# Circuit.net
KiCad netlist of a schematic drawn in EAGLE
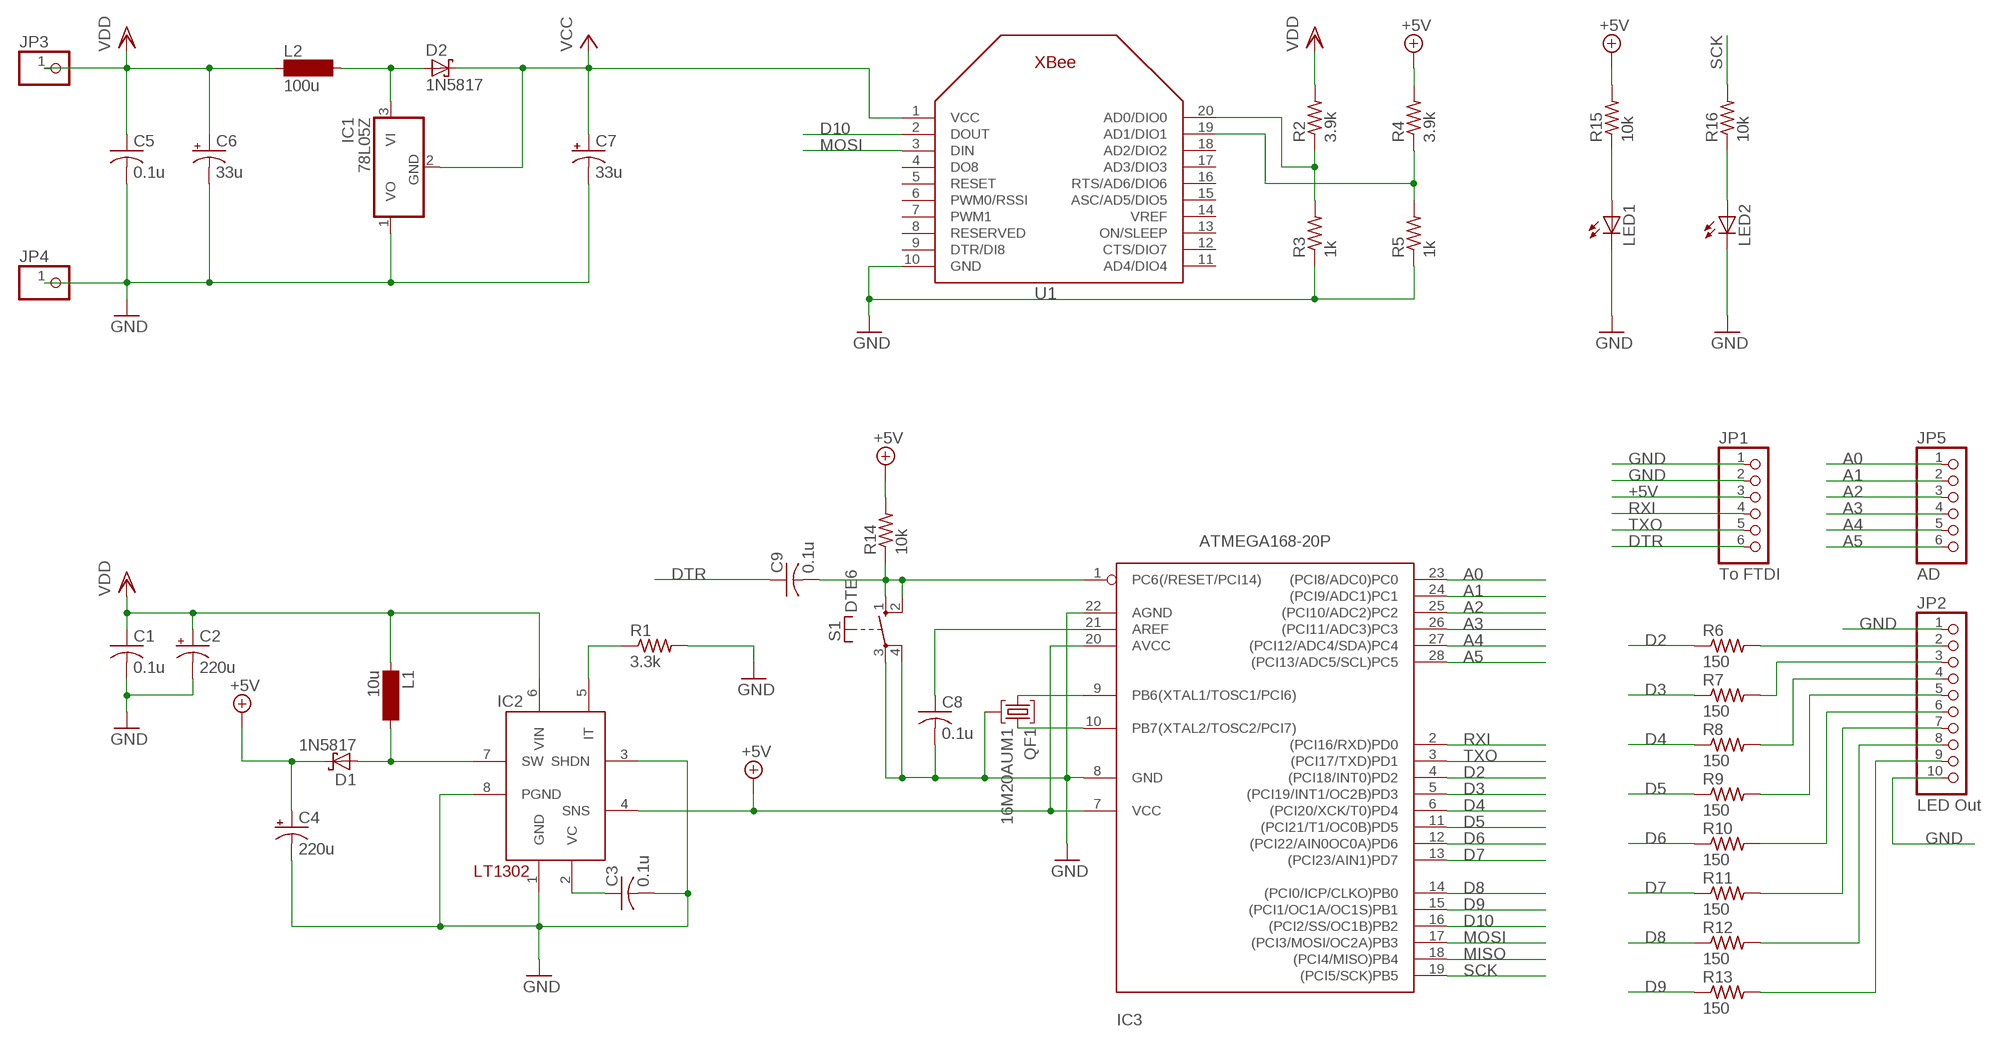
[diagram p0: schematic, sheet 1]

(export (version "E")
  (design (tool "Eeschema 10.0.6"))
  (components
    (comp (ref "C1")
      (value "0.1u")
      (footprint "eagle-import:C050-025X075")
      (libsource (lib "eagle-import") (part "C-US050-025X075"))
    )
    (comp (ref "C2")
      (value "220u")
      (footprint "eagle-import:E2,5-6")
      (libsource (lib "eagle-import") (part "CPOL-USE2.5-6"))
    )
    (comp (ref "C3")
      (value "0.1u")
      (footprint "eagle-import:C050-025X075")
      (libsource (lib "eagle-import") (part "C-US050-025X075"))
    )
    (comp (ref "C4")
      (value "220u")
      (footprint "eagle-import:E2,5-6")
      (libsource (lib "eagle-import") (part "CPOL-USE2.5-6"))
    )
    (comp (ref "C5")
      (value "0.1u")
      (footprint "eagle-import:C050-025X075")
      (libsource (lib "eagle-import") (part "C-US050-025X075"))
    )
    (comp (ref "C6")
      (value "33u")
      (footprint "eagle-import:E2,5-5")
      (libsource (lib "eagle-import") (part "CPOL-USE2.5-5"))
    )
    (comp (ref "C7")
      (value "33u")
      (footprint "eagle-import:E2,5-5")
      (libsource (lib "eagle-import") (part "CPOL-USE2.5-5"))
    )
    (comp (ref "C8")
      (value "0.1u")
      (footprint "eagle-import:C050-025X075")
      (libsource (lib "eagle-import") (part "C-US050-025X075"))
    )
    (comp (ref "C9")
      (value "0.1u")
      (footprint "eagle-import:C050-025X075")
      (libsource (lib "eagle-import") (part "C-US050-025X075"))
    )
    (comp (ref "D1")
      (value "1N5817")
      (footprint "eagle-import:DO35-7")
      (libsource (lib "eagle-import") (part "SCHOTTKY-DIODEDO35-7"))
    )
    (comp (ref "D2")
      (value "1N5817")
      (footprint "eagle-import:DO41-10")
      (libsource (lib "eagle-import") (part "BAT49"))
    )
    (comp (ref "IC1")
      (value "78L05Z")
      (footprint "eagle-import:TO92")
      (libsource (lib "eagle-import") (part "78ZL05"))
    )
    (comp (ref "IC2")
      (value "LT1302")
      (footprint "eagle-import:DIL08")
      (libsource (lib "eagle-import") (part "LT1302"))
    )
    (comp (ref "IC3")
      (value "ATMEGA168-20P")
      (footprint "eagle-import:DIL28-3")
      (libsource (lib "eagle-import") (part "ATMEGA168P-20"))
    )
    (comp (ref "JP1")
      (value "To FTDI")
      (footprint "eagle-import:1X06")
      (libsource (lib "eagle-import") (part "PINHD-1X6"))
    )
    (comp (ref "JP2")
      (value "LED Out")
      (footprint "eagle-import:1X10-BIG")
      (libsource (lib "eagle-import") (part "PINHD-1X10"))
    )
    (comp (ref "JP3")
      (value "PINHD-1X1")
      (footprint "eagle-import:1X01")
      (libsource (lib "eagle-import") (part "PINHD-1X1"))
    )
    (comp (ref "JP4")
      (value "PINHD-1X1")
      (footprint "eagle-import:1X01")
      (libsource (lib "eagle-import") (part "PINHD-1X1"))
    )
    (comp (ref "JP5")
      (value "AD")
      (footprint "eagle-import:1X06")
      (libsource (lib "eagle-import") (part "PINHD-1X6"))
    )
    (comp (ref "L1")
      (value "10u")
      (footprint "eagle-import:BS11")
      (libsource (lib "eagle-import") (part "BS11"))
    )
    (comp (ref "L2")
      (value "100u")
      (footprint "eagle-import:BS11")
      (fields (field (name "OC_FARNELL") "unknown") (field (name "OC_NEWARK") "unknown"))
      (libsource (lib "eagle-import") (part "BS11"))
    )
    (comp (ref "LED1")
      (value "LED3MM")
      (footprint "eagle-import:LED3MM")
      (libsource (lib "eagle-import") (part "LED3MM"))
    )
    (comp (ref "LED2")
      (value "LED3MM")
      (footprint "eagle-import:LED3MM")
      (libsource (lib "eagle-import") (part "LED3MM"))
    )
    (comp (ref "QF1")
      (value "16M20AUM1")
      (footprint "eagle-import:UM1")
      (libsource (lib "eagle-import") (part "16M20AUM1"))
    )
    (comp (ref "R1")
      (value "3.3k")
      (footprint "eagle-import:0204_7")
      (libsource (lib "eagle-import") (part "R-US_0204/7"))
    )
    (comp (ref "R2")
      (value "3.9k")
      (footprint "eagle-import:0207_7")
      (libsource (lib "eagle-import") (part "resistor_R-US_0207/7"))
    )
    (comp (ref "R3")
      (value "1k")
      (footprint "eagle-import:0207_7")
      (libsource (lib "eagle-import") (part "resistor_R-US_0207/7"))
    )
    (comp (ref "R4")
      (value "3.9k")
      (footprint "eagle-import:0207_7")
      (libsource (lib "eagle-import") (part "resistor_R-US_0207/7"))
    )
    (comp (ref "R5")
      (value "1k")
      (footprint "eagle-import:0207_7")
      (libsource (lib "eagle-import") (part "resistor_R-US_0207/7"))
    )
    (comp (ref "R6")
      (value "150")
      (footprint "eagle-import:0204_7")
      (libsource (lib "eagle-import") (part "R-US_0204/7"))
    )
    (comp (ref "R7")
      (value "150")
      (footprint "eagle-import:0204_7")
      (libsource (lib "eagle-import") (part "R-US_0204/7"))
    )
    (comp (ref "R8")
      (value "150")
      (footprint "eagle-import:0204_7")
      (libsource (lib "eagle-import") (part "R-US_0204/7"))
    )
    (comp (ref "R9")
      (value "150")
      (footprint "eagle-import:0204_7")
      (libsource (lib "eagle-import") (part "R-US_0204/7"))
    )
    (comp (ref "R10")
      (value "150")
      (footprint "eagle-import:0204_7")
      (libsource (lib "eagle-import") (part "R-US_0204/7"))
    )
    (comp (ref "R11")
      (value "150")
      (footprint "eagle-import:0204_7")
      (libsource (lib "eagle-import") (part "R-US_0204/7"))
    )
    (comp (ref "R12")
      (value "150")
      (footprint "eagle-import:0204_7")
      (libsource (lib "eagle-import") (part "R-US_0204/7"))
    )
    (comp (ref "R13")
      (value "150")
      (footprint "eagle-import:0204_7")
      (libsource (lib "eagle-import") (part "R-US_0204/7"))
    )
    (comp (ref "R14")
      (value "10k")
      (footprint "eagle-import:0204_7")
      (libsource (lib "eagle-import") (part "R-US_0204/7"))
    )
    (comp (ref "R15")
      (value "10k")
      (footprint "eagle-import:0207_7")
      (libsource (lib "eagle-import") (part "resistor_R-US_0207/7"))
    )
    (comp (ref "R16")
      (value "10k")
      (footprint "eagle-import:0207_7")
      (libsource (lib "eagle-import") (part "resistor_R-US_0207/7"))
    )
    (comp (ref "S1")
      (value "DTE6")
      (footprint "eagle-import:DTE6")
      (libsource (lib "eagle-import") (part "DTE6"))
    )
    (comp (ref "U1")
      (value "XBEE")
      (footprint "eagle-import:XBEE")
      (libsource (lib "eagle-import") (part "XBEE"))
    )
  )
  (nets
    (net (code "1") (name "+5V") (class "Default")
      (node (ref "C4") (pin "+") (pinfunction "+_+") (pintype "passive"))
      (node (ref "D1") (pin "C") (pinfunction "C_C") (pintype "passive"))
      (node (ref "IC2") (pin "4") (pinfunction "SNS_4") (pintype "passive"))
      (node (ref "IC3") (pin "20") (pinfunction "AVCC_20") (pintype "bidirectional"))
      (node (ref "IC3") (pin "7") (pinfunction "VCC_7") (pintype "bidirectional"))
      (node (ref "JP1") (pin "3") (pinfunction "3_3") (pintype "passive"))
      (node (ref "R14") (pin "2") (pinfunction "2_2") (pintype "passive"))
      (node (ref "R15") (pin "2") (pinfunction "2_2") (pintype "passive"))
      (node (ref "R4") (pin "2") (pinfunction "2_2") (pintype "passive"))
    )
    (net (code "2") (name "/A0") (class "Default")
      (node (ref "IC3") (pin "23") (pinfunction "(PCI8/ADC0)PC0_23") (pintype "bidirectional"))
      (node (ref "JP5") (pin "1") (pinfunction "1_1") (pintype "passive"))
    )
    (net (code "3") (name "/A1") (class "Default")
      (node (ref "IC3") (pin "24") (pinfunction "(PCI9/ADC1)PC1_24") (pintype "bidirectional"))
      (node (ref "JP5") (pin "2") (pinfunction "2_2") (pintype "passive"))
    )
    (net (code "4") (name "/A2") (class "Default")
      (node (ref "IC3") (pin "25") (pinfunction "(PCI10/ADC2)PC2_25") (pintype "bidirectional"))
      (node (ref "JP5") (pin "3") (pinfunction "3_3") (pintype "passive"))
    )
    (net (code "5") (name "/A3") (class "Default")
      (node (ref "IC3") (pin "26") (pinfunction "(PCI11/ADC3)PC3_26") (pintype "bidirectional"))
      (node (ref "JP5") (pin "4") (pinfunction "4_4") (pintype "passive"))
    )
    (net (code "6") (name "/A4") (class "Default")
      (node (ref "IC3") (pin "27") (pinfunction "(PCI12/ADC4/SDA)PC4_27") (pintype "bidirectional"))
      (node (ref "JP5") (pin "5") (pinfunction "5_5") (pintype "passive"))
    )
    (net (code "7") (name "/A5") (class "Default")
      (node (ref "IC3") (pin "28") (pinfunction "(PCI13/ADC5/SCL)PC5_28") (pintype "bidirectional"))
      (node (ref "JP5") (pin "6") (pinfunction "6_6") (pintype "passive"))
    )
    (net (code "8") (name "/D2") (class "Default")
      (node (ref "IC3") (pin "4") (pinfunction "(PCI18/INT0)PD2_4") (pintype "bidirectional"))
      (node (ref "R6") (pin "1") (pinfunction "1_1") (pintype "passive"))
    )
    (net (code "9") (name "/D3") (class "Default")
      (node (ref "IC3") (pin "5") (pinfunction "(PCI19/INT1/OC2B)PD3_5") (pintype "bidirectional"))
      (node (ref "R7") (pin "1") (pinfunction "1_1") (pintype "passive"))
    )
    (net (code "10") (name "/D4") (class "Default")
      (node (ref "IC3") (pin "6") (pinfunction "(PCI20/XCK/T0)PD4_6") (pintype "bidirectional"))
      (node (ref "R8") (pin "1") (pinfunction "1_1") (pintype "passive"))
    )
    (net (code "11") (name "/D5") (class "Default")
      (node (ref "IC3") (pin "11") (pinfunction "(PCI21/T1/OC0B)PD5_11") (pintype "bidirectional"))
      (node (ref "R9") (pin "1") (pinfunction "1_1") (pintype "passive"))
    )
    (net (code "12") (name "/D6") (class "Default")
      (node (ref "IC3") (pin "12") (pinfunction "(PCI22/AIN0OC0A)PD6_12") (pintype "bidirectional"))
      (node (ref "R10") (pin "1") (pinfunction "1_1") (pintype "passive"))
    )
    (net (code "13") (name "/D7") (class "Default")
      (node (ref "IC3") (pin "13") (pinfunction "(PCI23/AIN1)PD7_13") (pintype "bidirectional"))
      (node (ref "R11") (pin "1") (pinfunction "1_1") (pintype "passive"))
    )
    (net (code "14") (name "/D8") (class "Default")
      (node (ref "IC3") (pin "14") (pinfunction "(PCI0/ICP/CLKO)PB0_14") (pintype "bidirectional"))
      (node (ref "R12") (pin "1") (pinfunction "1_1") (pintype "passive"))
    )
    (net (code "15") (name "/D9") (class "Default")
      (node (ref "IC3") (pin "15") (pinfunction "(PCI1/OC1A/OC1S)PB1_15") (pintype "bidirectional"))
      (node (ref "R13") (pin "1") (pinfunction "1_1") (pintype "passive"))
    )
    (net (code "16") (name "/D10") (class "Default")
      (node (ref "IC3") (pin "16") (pinfunction "(PCI2/SS/OC1B)PB2_16") (pintype "bidirectional"))
      (node (ref "U1") (pin "2") (pinfunction "DOUT_2") (pintype "output"))
    )
    (net (code "17") (name "/DTR") (class "Default")
      (node (ref "C9") (pin "1") (pinfunction "1_1") (pintype "passive"))
      (node (ref "JP1") (pin "6") (pinfunction "6_6") (pintype "passive"))
    )
    (net (code "18") (name "/MISO") (class "Default")
      (node (ref "IC3") (pin "18") (pinfunction "(PCI4/MISO)PB4_18") (pintype "bidirectional"))
    )
    (net (code "19") (name "/MOSI") (class "Default")
      (node (ref "IC3") (pin "17") (pinfunction "(PCI3/MOSI/OC2A)PB3_17") (pintype "bidirectional"))
      (node (ref "U1") (pin "3") (pinfunction "DIN_3") (pintype "input"))
    )
    (net (code "20") (name "/RXI") (class "Default")
      (node (ref "IC3") (pin "2") (pinfunction "(PCI16/RXD)PD0_2") (pintype "bidirectional"))
      (node (ref "JP1") (pin "4") (pinfunction "4_4") (pintype "passive"))
    )
    (net (code "21") (name "/SCK") (class "Default")
      (node (ref "IC3") (pin "19") (pinfunction "(PCI5/SCK)PB5_19") (pintype "bidirectional"))
      (node (ref "R16") (pin "2") (pinfunction "2_2") (pintype "passive"))
    )
    (net (code "22") (name "/TXO") (class "Default")
      (node (ref "IC3") (pin "3") (pinfunction "(PCI17/TXD)PD1_3") (pintype "bidirectional"))
      (node (ref "JP1") (pin "5") (pinfunction "5_5") (pintype "passive"))
    )
    (net (code "23") (name "GND") (class "Default")
      (node (ref "C1") (pin "2") (pinfunction "2_2") (pintype "passive"))
      (node (ref "C2") (pin "-") (pinfunction "-_-") (pintype "passive"))
      (node (ref "C3") (pin "2") (pinfunction "2_2") (pintype "passive"))
      (node (ref "C4") (pin "-") (pinfunction "-_-") (pintype "passive"))
      (node (ref "C5") (pin "2") (pinfunction "2_2") (pintype "passive"))
      (node (ref "C6") (pin "-") (pinfunction "-_-") (pintype "passive"))
      (node (ref "C7") (pin "-") (pinfunction "-_-") (pintype "passive"))
      (node (ref "C8") (pin "2") (pinfunction "2_2") (pintype "passive"))
      (node (ref "IC1") (pin "1") (pinfunction "VO_1") (pintype "passive"))
      (node (ref "IC2") (pin "1") (pinfunction "GND_1") (pintype "input"))
      (node (ref "IC2") (pin "3") (pinfunction "SHDN_3") (pintype "input"))
      (node (ref "IC2") (pin "8") (pinfunction "PGND_8") (pintype "input"))
      (node (ref "IC3") (pin "22") (pinfunction "AGND_22") (pintype "bidirectional"))
      (node (ref "IC3") (pin "8") (pinfunction "GND_8") (pintype "bidirectional"))
      (node (ref "JP1") (pin "1") (pinfunction "1_1") (pintype "passive"))
      (node (ref "JP1") (pin "2") (pinfunction "2_2") (pintype "passive"))
      (node (ref "JP2") (pin "1") (pinfunction "1_1") (pintype "passive"))
      (node (ref "JP2") (pin "10") (pinfunction "10_10") (pintype "passive"))
      (node (ref "JP4") (pin "1") (pinfunction "1_1") (pintype "passive"))
      (node (ref "LED1") (pin "K") (pinfunction "C_K") (pintype "passive"))
      (node (ref "LED2") (pin "K") (pinfunction "C_K") (pintype "passive"))
      (node (ref "QF1") (pin "2") (pinfunction "2_2") (pintype "passive"))
      (node (ref "R1") (pin "2") (pinfunction "2_2") (pintype "passive"))
      (node (ref "R3") (pin "1") (pinfunction "1_1") (pintype "passive"))
      (node (ref "R5") (pin "1") (pinfunction "1_1") (pintype "passive"))
      (node (ref "S1") (pin "3") (pinfunction "P_3") (pintype "passive"))
      (node (ref "S1") (pin "4") (pinfunction "P_4") (pintype "passive"))
      (node (ref "U1") (pin "10") (pinfunction "GND_10") (pintype "power_in"))
    )
    (net (code "24") (name "Net-(IC1-VI)") (class "Default")
      (node (ref "D2") (pin "A") (pinfunction "A_A") (pintype "passive"))
      (node (ref "IC1") (pin "3") (pinfunction "VI_3") (pintype "input"))
      (node (ref "L2") (pin "2") (pinfunction "2_2") (pintype "passive"))
    )
    (net (code "25") (name "Net-(IC2-IT)") (class "Default")
      (node (ref "IC2") (pin "5") (pinfunction "IT_5") (pintype "input"))
      (node (ref "R1") (pin "1") (pinfunction "1_1") (pintype "passive"))
    )
    (net (code "26") (name "Net-(IC2-SW)") (class "Default")
      (node (ref "D1") (pin "A") (pinfunction "A_A") (pintype "passive"))
      (node (ref "IC2") (pin "7") (pinfunction "SW_7") (pintype "input"))
      (node (ref "L1") (pin "2") (pinfunction "2_2") (pintype "passive"))
    )
    (net (code "27") (name "Net-(IC2-VC)") (class "Default")
      (node (ref "C3") (pin "1") (pinfunction "1_1") (pintype "passive"))
      (node (ref "IC2") (pin "2") (pinfunction "VC_2") (pintype "passive"))
    )
    (net (code "28") (name "Net-(IC3-AREF)") (class "Default")
      (node (ref "C8") (pin "1") (pinfunction "1_1") (pintype "passive"))
      (node (ref "IC3") (pin "21") (pinfunction "AREF_21") (pintype "bidirectional"))
    )
    (net (code "29") (name "Net-(IC3-PB6(XTAL1{slash}TOSC1{slash}PCI6))") (class "Default")
      (node (ref "IC3") (pin "9") (pinfunction "PB6(XTAL1/TOSC1/PCI6)_9") (pintype "bidirectional"))
      (node (ref "QF1") (pin "1") (pinfunction "1_1") (pintype "passive"))
    )
    (net (code "30") (name "Net-(IC3-PB7(XTAL2{slash}TOSC2{slash}PCI7))") (class "Default")
      (node (ref "IC3") (pin "10") (pinfunction "PB7(XTAL2/TOSC2/PCI7)_10") (pintype "bidirectional"))
      (node (ref "QF1") (pin "3") (pinfunction "3_3") (pintype "passive"))
    )
    (net (code "31") (name "Net-(IC3-PC6({slash}RESET{slash}PCI14))") (class "Default")
      (node (ref "C9") (pin "2") (pinfunction "2_2") (pintype "passive"))
      (node (ref "IC3") (pin "1") (pinfunction "PC6(/RESET/PCI14)_1") (pintype "bidirectional"))
      (node (ref "R14") (pin "1") (pinfunction "1_1") (pintype "passive"))
      (node (ref "S1") (pin "1") (pinfunction "S_1") (pintype "passive"))
      (node (ref "S1") (pin "2") (pinfunction "S_2") (pintype "passive"))
    )
    (net (code "32") (name "Net-(JP2-Pad2)") (class "Default")
      (node (ref "JP2") (pin "2") (pinfunction "2_2") (pintype "passive"))
      (node (ref "R6") (pin "2") (pinfunction "2_2") (pintype "passive"))
    )
    (net (code "33") (name "Net-(JP2-Pad3)") (class "Default")
      (node (ref "JP2") (pin "3") (pinfunction "3_3") (pintype "passive"))
      (node (ref "R7") (pin "2") (pinfunction "2_2") (pintype "passive"))
    )
    (net (code "34") (name "Net-(JP2-Pad4)") (class "Default")
      (node (ref "JP2") (pin "4") (pinfunction "4_4") (pintype "passive"))
      (node (ref "R8") (pin "2") (pinfunction "2_2") (pintype "passive"))
    )
    (net (code "35") (name "Net-(JP2-Pad5)") (class "Default")
      (node (ref "JP2") (pin "5") (pinfunction "5_5") (pintype "passive"))
      (node (ref "R9") (pin "2") (pinfunction "2_2") (pintype "passive"))
    )
    (net (code "36") (name "Net-(JP2-Pad6)") (class "Default")
      (node (ref "JP2") (pin "6") (pinfunction "6_6") (pintype "passive"))
      (node (ref "R10") (pin "2") (pinfunction "2_2") (pintype "passive"))
    )
    (net (code "37") (name "Net-(JP2-Pad7)") (class "Default")
      (node (ref "JP2") (pin "7") (pinfunction "7_7") (pintype "passive"))
      (node (ref "R11") (pin "2") (pinfunction "2_2") (pintype "passive"))
    )
    (net (code "38") (name "Net-(JP2-Pad8)") (class "Default")
      (node (ref "JP2") (pin "8") (pinfunction "8_8") (pintype "passive"))
      (node (ref "R12") (pin "2") (pinfunction "2_2") (pintype "passive"))
    )
    (net (code "39") (name "Net-(JP2-Pad9)") (class "Default")
      (node (ref "JP2") (pin "9") (pinfunction "9_9") (pintype "passive"))
      (node (ref "R13") (pin "2") (pinfunction "2_2") (pintype "passive"))
    )
    (net (code "40") (name "Net-(LED1-PadA)") (class "Default")
      (node (ref "LED1") (pin "A") (pinfunction "A_A") (pintype "passive"))
      (node (ref "R15") (pin "1") (pinfunction "1_1") (pintype "passive"))
    )
    (net (code "41") (name "Net-(LED2-PadA)") (class "Default")
      (node (ref "LED2") (pin "A") (pinfunction "A_A") (pintype "passive"))
      (node (ref "R16") (pin "1") (pinfunction "1_1") (pintype "passive"))
    )
    (net (code "42") (name "Net-(U1-AD0{slash}DIO0)") (class "Default")
      (node (ref "R2") (pin "1") (pinfunction "1_1") (pintype "passive"))
      (node (ref "R3") (pin "2") (pinfunction "2_2") (pintype "passive"))
      (node (ref "U1") (pin "20") (pinfunction "AD0/DIO0_20") (pintype "bidirectional"))
    )
    (net (code "43") (name "Net-(U1-AD1{slash}DIO1)") (class "Default")
      (node (ref "R4") (pin "1") (pinfunction "1_1") (pintype "passive"))
      (node (ref "R5") (pin "2") (pinfunction "2_2") (pintype "passive"))
      (node (ref "U1") (pin "19") (pinfunction "AD1/DIO1_19") (pintype "bidirectional"))
    )
    (net (code "44") (name "VCC") (class "Default")
      (node (ref "C7") (pin "+") (pinfunction "+_+") (pintype "passive"))
      (node (ref "D2") (pin "C") (pinfunction "C_C") (pintype "passive"))
      (node (ref "IC1") (pin "2") (pinfunction "GND_2") (pintype "passive"))
      (node (ref "U1") (pin "1") (pinfunction "VCC_1") (pintype "power_in"))
    )
    (net (code "45") (name "VDD") (class "Default")
      (node (ref "C1") (pin "1") (pinfunction "1_1") (pintype "passive"))
      (node (ref "C2") (pin "+") (pinfunction "+_+") (pintype "passive"))
      (node (ref "C5") (pin "1") (pinfunction "1_1") (pintype "passive"))
      (node (ref "C6") (pin "+") (pinfunction "+_+") (pintype "passive"))
      (node (ref "IC2") (pin "6") (pinfunction "VIN_6") (pintype "input"))
      (node (ref "JP3") (pin "1") (pinfunction "1_1") (pintype "passive"))
      (node (ref "L1") (pin "1") (pinfunction "1_1") (pintype "passive"))
      (node (ref "L2") (pin "1") (pinfunction "1_1") (pintype "passive"))
      (node (ref "R2") (pin "2") (pinfunction "2_2") (pintype "passive"))
    )
    (net (code "46") (name "unconnected-(U1-AD2{slash}DIO2-Pad18)") (class "Default")
      (node (ref "U1") (pin "18") (pinfunction "AD2/DIO2_18") (pintype "bidirectional"))
    )
    (net (code "47") (name "unconnected-(U1-AD3{slash}DIO3-Pad17)") (class "Default")
      (node (ref "U1") (pin "17") (pinfunction "AD3/DIO3_17") (pintype "bidirectional"))
    )
    (net (code "48") (name "unconnected-(U1-AD4{slash}DIO4-Pad11)") (class "Default")
      (node (ref "U1") (pin "11") (pinfunction "AD4/DIO4_11") (pintype "bidirectional"))
    )
    (net (code "49") (name "unconnected-(U1-ASC{slash}AD5{slash}DIO5-Pad15)") (class "Default")
      (node (ref "U1") (pin "15") (pinfunction "ASC/AD5/DIO5_15") (pintype "bidirectional"))
    )
    (net (code "50") (name "unconnected-(U1-CTS{slash}DIO7-Pad12)") (class "Default")
      (node (ref "U1") (pin "12") (pinfunction "CTS/DIO7_12") (pintype "bidirectional"))
    )
    (net (code "51") (name "unconnected-(U1-DO8-Pad4)") (class "Default")
      (node (ref "U1") (pin "4") (pinfunction "DO8_4") (pintype "output"))
    )
    (net (code "52") (name "unconnected-(U1-DTR{slash}DI8-Pad9)") (class "Default")
      (node (ref "U1") (pin "9") (pinfunction "DTR/DI8_9") (pintype "input"))
    )
    (net (code "53") (name "unconnected-(U1-ON{slash}SLEEP-Pad13)") (class "Default")
      (node (ref "U1") (pin "13") (pinfunction "ON/SLEEP_13") (pintype "output"))
    )
    (net (code "54") (name "unconnected-(U1-PWM0{slash}RSSI-Pad6)") (class "Default")
      (node (ref "U1") (pin "6") (pinfunction "PWM0/RSSI_6") (pintype "output"))
    )
    (net (code "55") (name "unconnected-(U1-PWM1-Pad7)") (class "Default")
      (node (ref "U1") (pin "7") (pinfunction "PWM1_7") (pintype "output"))
    )
    (net (code "56") (name "unconnected-(U1-RESERVED-Pad8)") (class "Default")
      (node (ref "U1") (pin "8") (pinfunction "RESERVED_8") (pintype "no_connect"))
    )
    (net (code "57") (name "unconnected-(U1-RESET-Pad5)") (class "Default")
      (node (ref "U1") (pin "5") (pinfunction "RESET_5") (pintype "input"))
    )
    (net (code "58") (name "unconnected-(U1-RTS{slash}AD6{slash}DIO6-Pad16)") (class "Default")
      (node (ref "U1") (pin "16") (pinfunction "RTS/AD6/DIO6_16") (pintype "bidirectional"))
    )
    (net (code "59") (name "unconnected-(U1-VREF-Pad14)") (class "Default")
      (node (ref "U1") (pin "14") (pinfunction "VREF_14") (pintype "input"))
    )
  )
)
